# esp32-v7.net
KiCad netlist of a schematic drawn in EasyEDA Pro
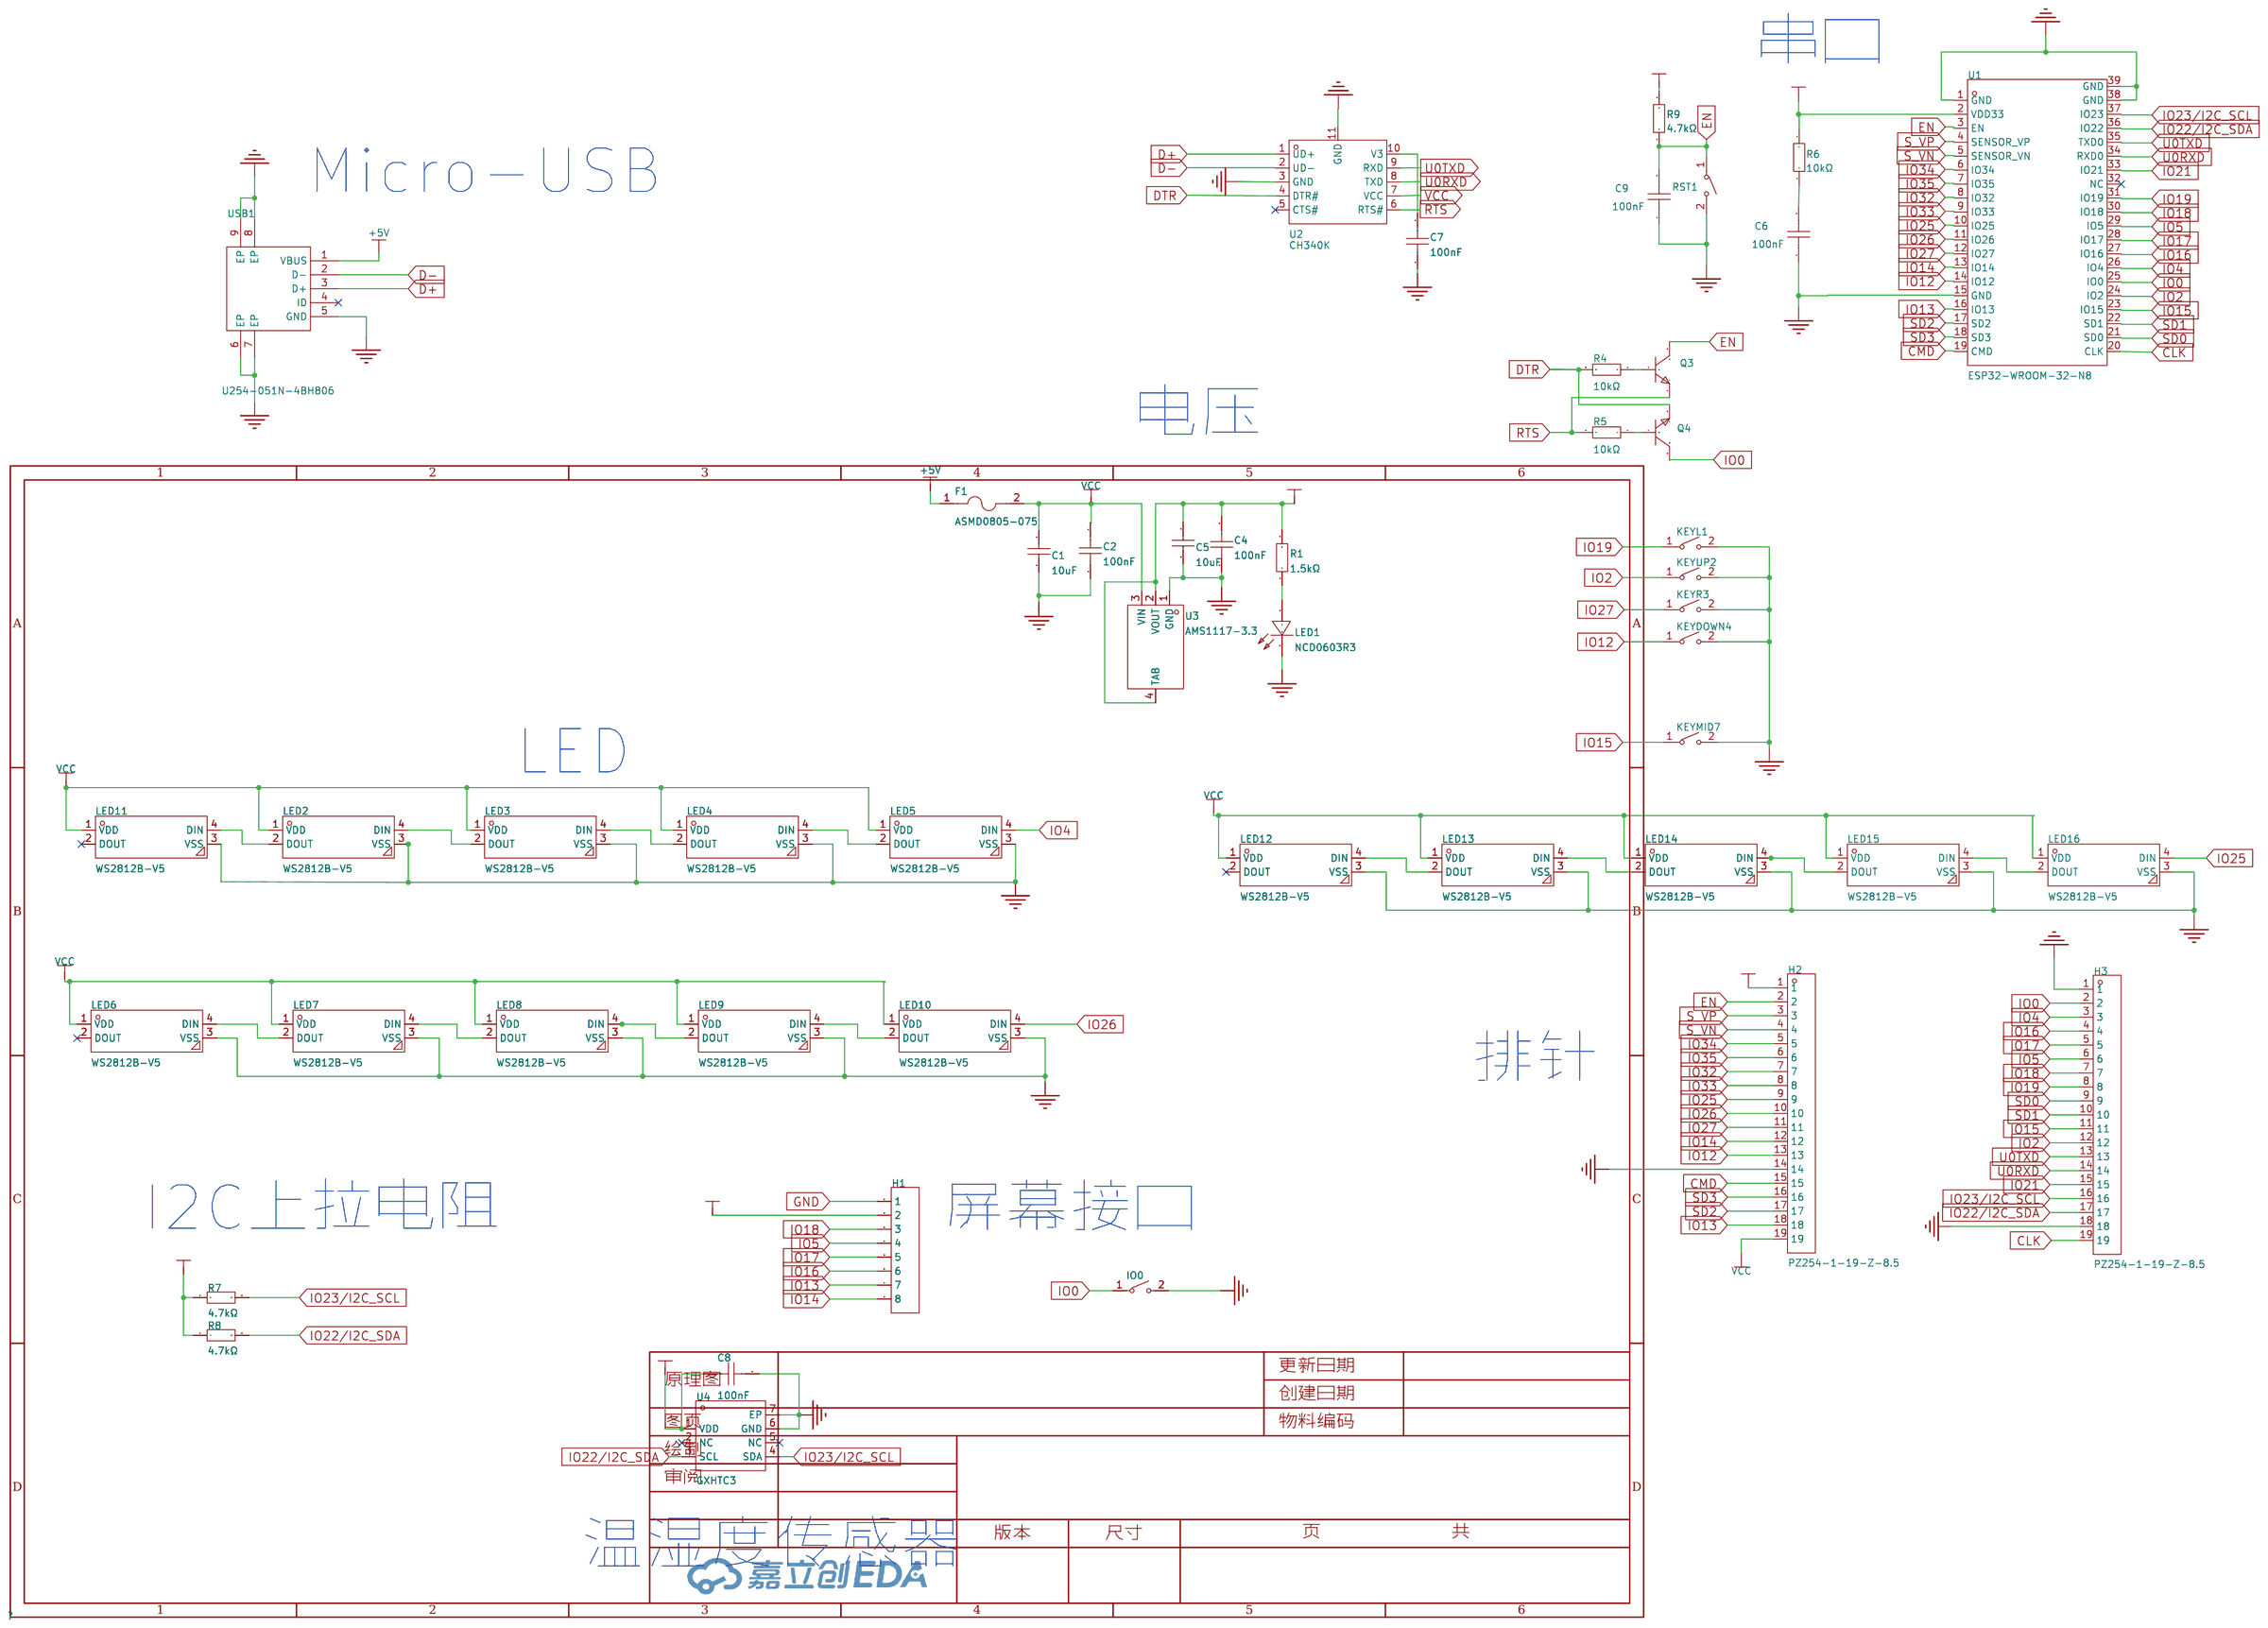
[diagram p0: schematic sheet]

(export (version "E")
  (design (tool "Eeschema 10.0.6"))
  (components
    (comp (ref "C1")
      (value "10uF")
      (footprint "easyedapro:C0805")
      (description "容值:10uF;精度:±10%;额定电压:16V;材质(温度系数):X5R;")
      (fields
        (field (name "Manufacturer Part") "CL21A106KOQNNNE")
        (field (name "Manufacturer") "SAMSUNG(三星)")
      )
      (libsource (lib "easyedapro") (part "CL21A106KOQNNNE"))
    )
    (comp (ref "C2")
      (value "100nF")
      (footprint "easyedapro:C0603")
      (description "容值:100nF;精度:±10%;额定电压:50V;材质(温度系数):X7R;")
      (fields
        (field (name "Manufacturer Part") "CC0603KRX7R9BB104")
        (field (name "Manufacturer") "YAGEO(国巨)")
      )
      (libsource (lib "easyedapro") (part "CC0603KRX7R9BB104"))
    )
    (comp (ref "C4")
      (value "100nF")
      (footprint "easyedapro:C0603")
      (description "容值:100nF;精度:±10%;额定电压:50V;材质(温度系数):X7R;")
      (fields
        (field (name "Manufacturer Part") "CC0603KRX7R9BB104")
        (field (name "Manufacturer") "YAGEO(国巨)")
      )
      (libsource (lib "easyedapro") (part "CC0603KRX7R9BB104"))
    )
    (comp (ref "C5")
      (value "10uF")
      (footprint "easyedapro:C0805")
      (description "容值:10uF;精度:±10%;额定电压:16V;材质(温度系数):X5R;")
      (fields
        (field (name "Manufacturer Part") "CL21A106KOQNNNE")
        (field (name "Manufacturer") "SAMSUNG(三星)")
      )
      (libsource (lib "easyedapro") (part "CL21A106KOQNNNE"))
    )
    (comp (ref "C6")
      (value "100nF")
      (footprint "easyedapro:C0603")
      (description "容值:100nF;精度:±10%;额定电压:50V;材质(温度系数):X7R;")
      (fields
        (field (name "Manufacturer Part") "CC0603KRX7R9BB104")
        (field (name "Manufacturer") "YAGEO(国巨)")
      )
      (libsource (lib "easyedapro") (part "CC0603KRX7R9BB104"))
    )
    (comp (ref "C7")
      (value "100nF")
      (footprint "easyedapro:C0603")
      (description "容值:100nF;精度:±10%;额定电压:50V;材质(温度系数):X7R;")
      (fields
        (field (name "Manufacturer Part") "CC0603KRX7R9BB104")
        (field (name "Manufacturer") "YAGEO(国巨)")
      )
      (libsource (lib "easyedapro") (part "CC0603KRX7R9BB104"))
    )
    (comp (ref "C8")
      (value "100nF")
      (footprint "easyedapro:C0603")
      (description "容值:100nF;精度:±10%;额定电压:50V;材质(温度系数):X7R;")
      (fields
        (field (name "Manufacturer Part") "CC0603KRX7R9BB104")
        (field (name "Manufacturer") "YAGEO(国巨)")
      )
      (libsource (lib "easyedapro") (part "CC0603KRX7R9BB104"))
    )
    (comp (ref "C9")
      (value "100nF")
      (footprint "easyedapro:C0603")
      (description "容值:100nF;精度:±10%;额定电压:50V;材质(温度系数):X7R;")
      (fields
        (field (name "Manufacturer Part") "CC0603KRX7R9BB104")
        (field (name "Manufacturer") "YAGEO(国巨)")
      )
      (libsource (lib "easyedapro") (part "CC0603KRX7R9BB104"))
    )
    (comp (ref "F1")
      (value "ASMD0805-075")
      (footprint "easyedapro:F0805")
      (description "最大电压:6V;最大电流:40A;保持电流:750mA;跳闸电流:1.5A;")
      (fields (field (name "Manufacturer") "JDTfuse(集电通)"))
      (libsource (lib "easyedapro") (part "ASMD0805-075"))
    )
    (comp (ref "H1")
      (value "~")
      (footprint "easyedapro:HDR-TH_8P-P2.54-V-F-1")
      (libsource (lib "easyedapro") (part "Header-Female-2.54_1x8"))
    )
    (comp (ref "H2")
      (value "PZ254-1-19-Z-8.5")
      (footprint "easyedapro:HDR-TH_19P-P2.54-V-M")
      (fields (field (name "Manufacturer") "HCTL(华灿天禄)"))
      (libsource (lib "easyedapro") (part "PZ254-1-19-Z-8.5"))
    )
    (comp (ref "H3")
      (value "PZ254-1-19-Z-8.5")
      (footprint "easyedapro:HDR-TH_19P-P2.54-V-M")
      (fields (field (name "Manufacturer") "HCTL(华灿天禄)"))
      (libsource (lib "easyedapro") (part "PZ254-1-19-Z-8.5"))
    )
    (comp (ref "IO0")
      (value "TS-1088R-02526")
      (footprint "easyedapro:SW-SMD_L3.9-W3.0-P4.45")
      (description "电路结构:单刀单掷;按钮形状:圆形按钮;安装方式:立贴;开关长度:3.9mm;开关宽度:2.93mm;开关高度:2.5mm;触点电流:50mA;额定电压(DC):12V;带灯:-;机械寿命:-;")
      (fields (field (name "Manufacturer") "XUNPU(讯普)"))
      (libsource (lib "easyedapro") (part "TS-1088R-02526"))
    )
    (comp (ref "KEYDOWN4")
      (value "TS-1088R-02526")
      (footprint "easyedapro:SW-SMD_L3.9-W3.0-P4.45")
      (description "电路结构:单刀单掷;按钮形状:圆形按钮;安装方式:立贴;开关长度:3.9mm;开关宽度:2.93mm;开关高度:2.5mm;触点电流:50mA;额定电压(DC):12V;带灯:-;机械寿命:-;")
      (fields (field (name "Manufacturer") "XUNPU(讯普)"))
      (libsource (lib "easyedapro") (part "TS-1088R-02526"))
    )
    (comp (ref "KEYL1")
      (value "TS-1088R-02526")
      (footprint "easyedapro:SW-SMD_L3.9-W3.0-P4.45")
      (description "电路结构:单刀单掷;按钮形状:圆形按钮;安装方式:立贴;开关长度:3.9mm;开关宽度:2.93mm;开关高度:2.5mm;触点电流:50mA;额定电压(DC):12V;带灯:-;机械寿命:-;")
      (fields (field (name "Manufacturer") "XUNPU(讯普)"))
      (libsource (lib "easyedapro") (part "TS-1088R-02526"))
    )
    (comp (ref "KEYMID7")
      (value "TS-1088R-02526")
      (footprint "easyedapro:SW-SMD_L3.9-W3.0-P4.45")
      (description "电路结构:单刀单掷;按钮形状:圆形按钮;安装方式:立贴;开关长度:3.9mm;开关宽度:2.93mm;开关高度:2.5mm;触点电流:50mA;额定电压(DC):12V;带灯:-;机械寿命:-;")
      (fields (field (name "Manufacturer") "XUNPU(讯普)"))
      (libsource (lib "easyedapro") (part "TS-1088R-02526"))
    )
    (comp (ref "KEYR3")
      (value "TS-1088R-02526")
      (footprint "easyedapro:SW-SMD_L3.9-W3.0-P4.45")
      (description "电路结构:单刀单掷;按钮形状:圆形按钮;安装方式:立贴;开关长度:3.9mm;开关宽度:2.93mm;开关高度:2.5mm;触点电流:50mA;额定电压(DC):12V;带灯:-;机械寿命:-;")
      (fields (field (name "Manufacturer") "XUNPU(讯普)"))
      (libsource (lib "easyedapro") (part "TS-1088R-02526"))
    )
    (comp (ref "KEYUP2")
      (value "TS-1088R-02526")
      (footprint "easyedapro:SW-SMD_L3.9-W3.0-P4.45")
      (description "电路结构:单刀单掷;按钮形状:圆形按钮;安装方式:立贴;开关长度:3.9mm;开关宽度:2.93mm;开关高度:2.5mm;触点电流:50mA;额定电压(DC):12V;带灯:-;机械寿命:-;")
      (fields (field (name "Manufacturer") "XUNPU(讯普)"))
      (libsource (lib "easyedapro") (part "TS-1088R-02526"))
    )
    (comp (ref "LED1")
      (value "NCD0603R3")
      (footprint "easyedapro:LED0603-R-RD_RED")
      (fields (field (name "Manufacturer") "国星光电"))
      (libsource (lib "easyedapro") (part "NCD0603R3"))
    )
    (comp (ref "LED2")
      (value "WS2812B-V5")
      (footprint "easyedapro:LED-SMD_4P-L5.0-W5.0-LS5.4-TL-1")
      (description "（注意防潮，请查阅规格书中对应具体内容）")
      (fields (field (name "Manufacturer") "worldsemi"))
      (libsource (lib "easyedapro") (part "WS2812B-V5_C2846931"))
    )
    (comp (ref "LED3")
      (value "WS2812B-V5")
      (footprint "easyedapro:LED-SMD_4P-L5.0-W5.0-LS5.4-TL-1")
      (description "（注意防潮，请查阅规格书中对应具体内容）")
      (fields (field (name "Manufacturer") "worldsemi"))
      (libsource (lib "easyedapro") (part "WS2812B-V5_C2846931"))
    )
    (comp (ref "LED4")
      (value "WS2812B-V5")
      (footprint "easyedapro:LED-SMD_4P-L5.0-W5.0-LS5.4-TL-1")
      (description "（注意防潮，请查阅规格书中对应具体内容）")
      (fields (field (name "Manufacturer") "worldsemi"))
      (libsource (lib "easyedapro") (part "WS2812B-V5_C2846931"))
    )
    (comp (ref "LED5")
      (value "WS2812B-V5")
      (footprint "easyedapro:LED-SMD_4P-L5.0-W5.0-LS5.4-TL-1")
      (description "（注意防潮，请查阅规格书中对应具体内容）")
      (fields (field (name "Manufacturer") "worldsemi"))
      (libsource (lib "easyedapro") (part "WS2812B-V5_C2846931"))
    )
    (comp (ref "LED6")
      (value "WS2812B-V5")
      (footprint "easyedapro:LED-SMD_4P-L5.0-W5.0-LS5.4-TL-1")
      (description "（注意防潮，请查阅规格书中对应具体内容）")
      (fields (field (name "Manufacturer") "worldsemi"))
      (libsource (lib "easyedapro") (part "WS2812B-V5_C2846931"))
    )
    (comp (ref "LED7")
      (value "WS2812B-V5")
      (footprint "easyedapro:LED-SMD_4P-L5.0-W5.0-LS5.4-TL-1")
      (description "（注意防潮，请查阅规格书中对应具体内容）")
      (fields (field (name "Manufacturer") "worldsemi"))
      (libsource (lib "easyedapro") (part "WS2812B-V5_C2846931"))
    )
    (comp (ref "LED8")
      (value "WS2812B-V5")
      (footprint "easyedapro:LED-SMD_4P-L5.0-W5.0-LS5.4-TL-1")
      (description "（注意防潮，请查阅规格书中对应具体内容）")
      (fields (field (name "Manufacturer") "worldsemi"))
      (libsource (lib "easyedapro") (part "WS2812B-V5_C2846931"))
    )
    (comp (ref "LED9")
      (value "WS2812B-V5")
      (footprint "easyedapro:LED-SMD_4P-L5.0-W5.0-LS5.4-TL-1")
      (description "（注意防潮，请查阅规格书中对应具体内容）")
      (fields (field (name "Manufacturer") "worldsemi"))
      (libsource (lib "easyedapro") (part "WS2812B-V5_C2846931"))
    )
    (comp (ref "LED10")
      (value "WS2812B-V5")
      (footprint "easyedapro:LED-SMD_4P-L5.0-W5.0-LS5.4-TL-1")
      (description "（注意防潮，请查阅规格书中对应具体内容）")
      (fields (field (name "Manufacturer") "worldsemi"))
      (libsource (lib "easyedapro") (part "WS2812B-V5_C2846931"))
    )
    (comp (ref "LED11")
      (value "WS2812B-V5")
      (footprint "easyedapro:LED-SMD_4P-L5.0-W5.0-LS5.4-TL-1")
      (description "（注意防潮，请查阅规格书中对应具体内容）")
      (fields (field (name "Manufacturer") "worldsemi"))
      (libsource (lib "easyedapro") (part "WS2812B-V5_C2846931"))
    )
    (comp (ref "LED12")
      (value "WS2812B-V5")
      (footprint "easyedapro:LED-SMD_4P-L5.0-W5.0-LS5.4-TL-1")
      (description "（注意防潮，请查阅规格书中对应具体内容）")
      (fields (field (name "Manufacturer") "worldsemi"))
      (libsource (lib "easyedapro") (part "WS2812B-V5_C2846931"))
    )
    (comp (ref "LED13")
      (value "WS2812B-V5")
      (footprint "easyedapro:LED-SMD_4P-L5.0-W5.0-LS5.4-TL-1")
      (description "（注意防潮，请查阅规格书中对应具体内容）")
      (fields (field (name "Manufacturer") "worldsemi"))
      (libsource (lib "easyedapro") (part "WS2812B-V5_C2846931"))
    )
    (comp (ref "LED14")
      (value "WS2812B-V5")
      (footprint "easyedapro:LED-SMD_4P-L5.0-W5.0-LS5.4-TL-1")
      (description "（注意防潮，请查阅规格书中对应具体内容）")
      (fields (field (name "Manufacturer") "worldsemi"))
      (libsource (lib "easyedapro") (part "WS2812B-V5_C2846931"))
    )
    (comp (ref "LED15")
      (value "WS2812B-V5")
      (footprint "easyedapro:LED-SMD_4P-L5.0-W5.0-LS5.4-TL-1")
      (description "（注意防潮，请查阅规格书中对应具体内容）")
      (fields (field (name "Manufacturer") "worldsemi"))
      (libsource (lib "easyedapro") (part "WS2812B-V5_C2846931"))
    )
    (comp (ref "LED16")
      (value "WS2812B-V5")
      (footprint "easyedapro:LED-SMD_4P-L5.0-W5.0-LS5.4-TL-1")
      (description "（注意防潮，请查阅规格书中对应具体内容）")
      (fields (field (name "Manufacturer") "worldsemi"))
      (libsource (lib "easyedapro") (part "WS2812B-V5_C2846931"))
    )
    (comp (ref "Q3")
      (value "L8050QLT1G")
      (footprint "easyedapro:SOT-23-3_L2.9-W1.3-P1.90-LS2.4-BR")
      (description "晶体管类型:NPN;集电极电流(Ic):800mA;集射极击穿电压(Vceo):25V;功率(Pd):225mW;")
      (fields (field (name "Manufacturer") "LRC(乐山无线电)"))
      (libsource (lib "easyedapro") (part "L8050QLT1G"))
    )
    (comp (ref "Q4")
      (value "L8050QLT1G")
      (footprint "easyedapro:SOT-23-3_L2.9-W1.3-P1.90-LS2.4-BR")
      (description "晶体管类型:NPN;集电极电流(Ic):800mA;集射极击穿电压(Vceo):25V;功率(Pd):225mW;")
      (fields (field (name "Manufacturer") "LRC(乐山无线电)"))
      (libsource (lib "easyedapro") (part "L8050QLT1G"))
    )
    (comp (ref "R1")
      (value "1.5kΩ")
      (footprint "easyedapro:R0805")
      (description "电阻类型:厚膜电阻;阻值:1.5kΩ;精度:±1%;功率:125mW;最大工作电压:150V;温度系数:±100ppm/°C;")
      (fields
        (field (name "Manufacturer Part") "0805W8F1501T5E")
        (field (name "Manufacturer") "UNI-ROYAL(厚声)")
      )
      (libsource (lib "easyedapro") (part "0805W8F1501T5E"))
    )
    (comp (ref "R4")
      (value "10kΩ")
      (footprint "easyedapro:R0603")
      (description "电阻类型:薄膜电阻;阻值:10kΩ;精度:±0.1%;功率:100mW;温度系数:±25ppm/;最大工作电压:75V;工作温度范围:-55~+155;")
      (fields
        (field (name "Manufacturer Part") "TR0603B10K0P0525Z")
        (field (name "Manufacturer") "EVER OHMS(天二科技)")
      )
      (libsource (lib "easyedapro") (part "TR0603B10KP05250.1W"))
    )
    (comp (ref "R5")
      (value "10kΩ")
      (footprint "easyedapro:R0603")
      (description "电阻类型:薄膜电阻;阻值:10kΩ;精度:±0.1%;功率:100mW;温度系数:±25ppm/;最大工作电压:75V;工作温度范围:-55~+155;")
      (fields
        (field (name "Manufacturer Part") "TR0603B10K0P0525Z")
        (field (name "Manufacturer") "EVER OHMS(天二科技)")
      )
      (libsource (lib "easyedapro") (part "TR0603B10KP05250.1W"))
    )
    (comp (ref "R6")
      (value "10kΩ")
      (footprint "easyedapro:R0603")
      (description "电阻类型:薄膜电阻;阻值:10kΩ;精度:±0.1%;功率:100mW;温度系数:±25ppm/;最大工作电压:75V;工作温度范围:-55~+155;")
      (fields
        (field (name "Manufacturer Part") "TR0603B10K0P0525Z")
        (field (name "Manufacturer") "EVER OHMS(天二科技)")
      )
      (libsource (lib "easyedapro") (part "TR0603B10KP05250.1W"))
    )
    (comp (ref "R7")
      (value "4.7kΩ")
      (footprint "easyedapro:R0805")
      (description "电阻类型:厚膜电阻;阻值:4.7kΩ;精度:±1%;功率:125mW;最大工作电压:150V;温度系数:±100ppm/°C;")
      (fields
        (field (name "Manufacturer Part") "0805W8F4701T5E")
        (field (name "Manufacturer") "UNI-ROYAL(厚声)")
      )
      (libsource (lib "easyedapro") (part "0805W8F4701T5E"))
    )
    (comp (ref "R8")
      (value "4.7kΩ")
      (footprint "easyedapro:R0805")
      (description "电阻类型:厚膜电阻;阻值:4.7kΩ;精度:±1%;功率:125mW;最大工作电压:150V;温度系数:±100ppm/°C;")
      (fields
        (field (name "Manufacturer Part") "0805W8F4701T5E")
        (field (name "Manufacturer") "UNI-ROYAL(厚声)")
      )
      (libsource (lib "easyedapro") (part "0805W8F4701T5E"))
    )
    (comp (ref "R9")
      (value "4.7kΩ")
      (footprint "easyedapro:R0805")
      (description "电阻类型:厚膜电阻;阻值:4.7kΩ;精度:±1%;功率:125mW;最大工作电压:150V;温度系数:±100ppm/°C;")
      (fields
        (field (name "Manufacturer Part") "0805W8F4701T5E")
        (field (name "Manufacturer") "UNI-ROYAL(厚声)")
      )
      (libsource (lib "easyedapro") (part "0805W8F4701T5E"))
    )
    (comp (ref "RST1")
      (value "TS-1088R-02526")
      (footprint "easyedapro:SW-SMD_L3.9-W3.0-P4.45")
      (description "电路结构:单刀单掷;按钮形状:圆形按钮;安装方式:立贴;开关长度:3.9mm;开关宽度:2.93mm;开关高度:2.5mm;触点电流:50mA;额定电压(DC):12V;带灯:-;机械寿命:-;")
      (fields (field (name "Manufacturer") "XUNPU(讯普)"))
      (libsource (lib "easyedapro") (part "TS-1088R-02526"))
    )
    (comp (ref "U1")
      (value "ESP32-WROOM-32-N8")
      (footprint "easyedapro:WIFIM-SMD_39P-L25.5-W18.0-P1.27")
      (fields (field (name "Manufacturer") "ESPRESSIF(乐鑫)"))
      (libsource (lib "easyedapro") (part "ESP32-WROOM-32(8MB)"))
    )
    (comp (ref "U2")
      (value "CH340K")
      (footprint "easyedapro:ESOP-10_L4.9-W3.9-P1.00-LS6.0-BL-EP")
      (fields (field (name "Manufacturer") "WCH(南京沁恒)"))
      (libsource (lib "easyedapro") (part "CH340K_C18208922"))
    )
    (comp (ref "U3")
      (value "AMS1117-3.3")
      (footprint "easyedapro:SOT-223-3_L6.5-W3.4-P2.30-LS7.0-BR")
      (description "输出类型:固定;最大输入电压:18V;输出电压:3.3V;最大输出电流:800mA;电源纹波抑制比(PSRR):-;输出极性:正极;")
      (fields (field (name "Manufacturer") "PUOLOP(迪浦)"))
      (libsource (lib "easyedapro") (part "AMS1117-3.3_C351784"))
    )
    (comp (ref "U4")
      (value "GXHTC3")
      (footprint "easyedapro:DFN-6_L2.0-W2.0-P0.50-BL-EP")
      (fields (field (name "Manufacturer") "GXCAS(中科银河芯)"))
      (libsource (lib "easyedapro") (part "GXHTC3"))
    )
    (comp (ref "USB1")
      (value "U254-051N-4BH806")
      (footprint "easyedapro:MICRO-USB-SMD_U254-051N-4BH806")
      (fields (field (name "Manufacturer") "XKB Connectivity(中国星坤)"))
      (libsource (lib "easyedapro") (part "U254-051N-4BH806"))
    )
  )
  (nets
    (net (code "1") (name "+5V") (class "Default")
      (node (ref "F1") (pin "1") (pinfunction "1_1") (pintype "unspecified"))
      (node (ref "USB1") (pin "1") (pinfunction "VBUS_1") (pintype "unspecified"))
    )
    (net (code "2") (name "3V3") (class "Default")
      (node (ref "C4") (pin "2") (pinfunction "2_2") (pintype "unspecified"))
      (node (ref "C5") (pin "2") (pinfunction "2_2") (pintype "input"))
      (node (ref "C8") (pin "2") (pinfunction "2_2") (pintype "unspecified"))
      (node (ref "H1") (pin "2") (pinfunction "2_2") (pintype "input"))
      (node (ref "H2") (pin "1") (pinfunction "1_1") (pintype "unspecified"))
      (node (ref "R1") (pin "2") (pinfunction "2_2") (pintype "input"))
      (node (ref "R6") (pin "1") (pinfunction "1_1") (pintype "input"))
      (node (ref "R7") (pin "1") (pinfunction "1_1") (pintype "input"))
      (node (ref "R8") (pin "1") (pinfunction "1_1") (pintype "input"))
      (node (ref "R9") (pin "2") (pinfunction "2_2") (pintype "input"))
      (node (ref "U1") (pin "2") (pinfunction "VDD33_2") (pintype "unspecified"))
      (node (ref "U3") (pin "2") (pinfunction "VOUT_2") (pintype "unspecified"))
      (node (ref "U3") (pin "4") (pinfunction "TAB_4") (pintype "unspecified"))
      (node (ref "U4") (pin "1") (pinfunction "VDD_1") (pintype "unspecified"))
    )
    (net (code "3") (name "CLK") (class "Default")
      (node (ref "H3") (pin "19") (pinfunction "19_19") (pintype "unspecified"))
      (node (ref "U1") (pin "20") (pinfunction "CLK_20") (pintype "unspecified"))
    )
    (net (code "4") (name "CMD") (class "Default")
      (node (ref "H2") (pin "15") (pinfunction "15_15") (pintype "unspecified"))
      (node (ref "U1") (pin "19") (pinfunction "CMD_19") (pintype "unspecified"))
    )
    (net (code "5") (name "D+") (class "Default")
      (node (ref "U2") (pin "1") (pinfunction "UD+_1") (pintype "unspecified"))
      (node (ref "USB1") (pin "3") (pinfunction "D+_3") (pintype "unspecified"))
    )
    (net (code "6") (name "D-") (class "Default")
      (node (ref "USB1") (pin "2") (pinfunction "D-_2") (pintype "unspecified"))
    )
    (net (code "7") (name "DTR") (class "Default")
      (node (ref "Q4") (pin "2") (pinfunction "E_2") (pintype "unspecified"))
      (node (ref "R4") (pin "2") (pinfunction "2_2") (pintype "input"))
      (node (ref "U2") (pin "4") (pinfunction "DTR#_4") (pintype "unspecified"))
    )
    (net (code "8") (name "EN") (class "Default")
      (node (ref "C9") (pin "2") (pinfunction "2_2") (pintype "unspecified"))
      (node (ref "H2") (pin "2") (pinfunction "2_2") (pintype "unspecified"))
      (node (ref "Q3") (pin "3") (pinfunction "C_3") (pintype "unspecified"))
      (node (ref "R9") (pin "1") (pinfunction "1_1") (pintype "input"))
      (node (ref "RST1") (pin "1") (pinfunction "1_1") (pintype "unspecified"))
      (node (ref "U1") (pin "3") (pinfunction "EN_3") (pintype "unspecified"))
    )
    (net (code "9") (name "GND") (class "Default")
      (node (ref "C1") (pin "1") (pinfunction "1_1") (pintype "input"))
      (node (ref "C2") (pin "1") (pinfunction "1_1") (pintype "unspecified"))
      (node (ref "C4") (pin "1") (pinfunction "1_1") (pintype "unspecified"))
      (node (ref "C5") (pin "1") (pinfunction "1_1") (pintype "input"))
      (node (ref "C6") (pin "1") (pinfunction "1_1") (pintype "unspecified"))
      (node (ref "C7") (pin "1") (pinfunction "1_1") (pintype "unspecified"))
      (node (ref "C8") (pin "1") (pinfunction "1_1") (pintype "unspecified"))
      (node (ref "C9") (pin "1") (pinfunction "1_1") (pintype "unspecified"))
      (node (ref "H1") (pin "1") (pinfunction "1_1") (pintype "input"))
      (node (ref "H2") (pin "14") (pinfunction "14_14") (pintype "unspecified"))
      (node (ref "H3") (pin "1") (pinfunction "1_1") (pintype "unspecified"))
      (node (ref "H3") (pin "18") (pinfunction "18_18") (pintype "unspecified"))
      (node (ref "IO0") (pin "2") (pinfunction "2_2") (pintype "unspecified"))
      (node (ref "KEYDOWN4") (pin "2") (pinfunction "2_2") (pintype "unspecified"))
      (node (ref "KEYL1") (pin "2") (pinfunction "2_2") (pintype "unspecified"))
      (node (ref "KEYMID7") (pin "2") (pinfunction "2_2") (pintype "unspecified"))
      (node (ref "KEYR3") (pin "2") (pinfunction "2_2") (pintype "unspecified"))
      (node (ref "KEYUP2") (pin "2") (pinfunction "2_2") (pintype "unspecified"))
      (node (ref "LED1") (pin "2") (pinfunction "K_2") (pintype "unspecified"))
      (node (ref "LED10") (pin "3") (pinfunction "VSS_3") (pintype "unspecified"))
      (node (ref "LED11") (pin "3") (pinfunction "VSS_3") (pintype "unspecified"))
      (node (ref "LED12") (pin "3") (pinfunction "VSS_3") (pintype "unspecified"))
      (node (ref "LED13") (pin "3") (pinfunction "VSS_3") (pintype "unspecified"))
      (node (ref "LED14") (pin "3") (pinfunction "VSS_3") (pintype "unspecified"))
      (node (ref "LED15") (pin "3") (pinfunction "VSS_3") (pintype "unspecified"))
      (node (ref "LED16") (pin "3") (pinfunction "VSS_3") (pintype "unspecified"))
      (node (ref "LED2") (pin "3") (pinfunction "VSS_3") (pintype "unspecified"))
      (node (ref "LED3") (pin "3") (pinfunction "VSS_3") (pintype "unspecified"))
      (node (ref "LED4") (pin "3") (pinfunction "VSS_3") (pintype "unspecified"))
      (node (ref "LED5") (pin "3") (pinfunction "VSS_3") (pintype "unspecified"))
      (node (ref "LED6") (pin "3") (pinfunction "VSS_3") (pintype "unspecified"))
      (node (ref "LED7") (pin "3") (pinfunction "VSS_3") (pintype "unspecified"))
      (node (ref "LED8") (pin "3") (pinfunction "VSS_3") (pintype "unspecified"))
      (node (ref "LED9") (pin "3") (pinfunction "VSS_3") (pintype "unspecified"))
      (node (ref "RST1") (pin "2") (pinfunction "2_2") (pintype "unspecified"))
      (node (ref "U1") (pin "15") (pinfunction "GND_15") (pintype "unspecified"))
      (node (ref "U1") (pin "39") (pinfunction "GND_39") (pintype "unspecified"))
      (node (ref "U2") (pin "11") (pinfunction "GND_11") (pintype "unspecified"))
      (node (ref "U2") (pin "3") (pinfunction "GND_3") (pintype "unspecified"))
      (node (ref "U3") (pin "1") (pinfunction "GND_1") (pintype "unspecified"))
      (node (ref "U4") (pin "6") (pinfunction "GND_6") (pintype "unspecified"))
      (node (ref "U4") (pin "7") (pinfunction "EP_7") (pintype "unspecified"))
      (node (ref "USB1") (pin "5") (pinfunction "GND_5") (pintype "unspecified"))
      (node (ref "USB1") (pin "6") (pinfunction "EP_6") (pintype "unspecified"))
      (node (ref "USB1") (pin "7") (pinfunction "EP_7") (pintype "unspecified"))
      (node (ref "USB1") (pin "8") (pinfunction "EP_8") (pintype "unspecified"))
      (node (ref "USB1") (pin "9") (pinfunction "EP_9") (pintype "unspecified"))
    )
    (net (code "10") (name "IO0") (class "Default")
      (node (ref "H3") (pin "2") (pinfunction "2_2") (pintype "unspecified"))
      (node (ref "IO0") (pin "1") (pinfunction "1_1") (pintype "unspecified"))
      (node (ref "Q4") (pin "3") (pinfunction "C_3") (pintype "unspecified"))
    )
    (net (code "11") (name "IO2") (class "Default")
      (node (ref "H3") (pin "12") (pinfunction "12_12") (pintype "unspecified"))
      (node (ref "KEYUP2") (pin "1") (pinfunction "1_1") (pintype "unspecified"))
    )
    (net (code "12") (name "IO4") (class "Default")
      (node (ref "H3") (pin "3") (pinfunction "3_3") (pintype "unspecified"))
      (node (ref "LED5") (pin "4") (pinfunction "DIN_4") (pintype "unspecified"))
    )
    (net (code "13") (name "IO5") (class "Default")
      (node (ref "H1") (pin "4") (pinfunction "4_4") (pintype "input"))
      (node (ref "H3") (pin "6") (pinfunction "6_6") (pintype "unspecified"))
    )
    (net (code "14") (name "IO12") (class "Default")
      (node (ref "H2") (pin "13") (pinfunction "13_13") (pintype "unspecified"))
      (node (ref "KEYDOWN4") (pin "1") (pinfunction "1_1") (pintype "unspecified"))
      (node (ref "U1") (pin "14") (pinfunction "IO12_14") (pintype "unspecified"))
    )
    (net (code "15") (name "IO13") (class "Default")
      (node (ref "H1") (pin "7") (pinfunction "7_7") (pintype "input"))
      (node (ref "H2") (pin "18") (pinfunction "18_18") (pintype "unspecified"))
      (node (ref "U1") (pin "16") (pinfunction "IO13_16") (pintype "unspecified"))
    )
    (net (code "16") (name "IO14") (class "Default")
      (node (ref "H1") (pin "8") (pinfunction "8_8") (pintype "input"))
      (node (ref "H2") (pin "12") (pinfunction "12_12") (pintype "unspecified"))
      (node (ref "U1") (pin "13") (pinfunction "IO14_13") (pintype "unspecified"))
    )
    (net (code "17") (name "IO15") (class "Default")
      (node (ref "H3") (pin "11") (pinfunction "11_11") (pintype "unspecified"))
      (node (ref "KEYMID7") (pin "1") (pinfunction "1_1") (pintype "unspecified"))
    )
    (net (code "18") (name "IO16") (class "Default")
      (node (ref "H1") (pin "6") (pinfunction "6_6") (pintype "input"))
      (node (ref "H3") (pin "4") (pinfunction "4_4") (pintype "unspecified"))
    )
    (net (code "19") (name "IO17") (class "Default")
      (node (ref "H1") (pin "5") (pinfunction "5_5") (pintype "input"))
      (node (ref "H3") (pin "5") (pinfunction "5_5") (pintype "unspecified"))
    )
    (net (code "20") (name "IO18") (class "Default")
      (node (ref "H1") (pin "3") (pinfunction "3_3") (pintype "input"))
      (node (ref "H3") (pin "7") (pinfunction "7_7") (pintype "unspecified"))
    )
    (net (code "21") (name "IO19") (class "Default")
      (node (ref "H3") (pin "8") (pinfunction "8_8") (pintype "unspecified"))
      (node (ref "KEYL1") (pin "1") (pinfunction "1_1") (pintype "unspecified"))
    )
    (net (code "22") (name "IO21") (class "Default")
      (node (ref "H3") (pin "15") (pinfunction "15_15") (pintype "unspecified"))
    )
    (net (code "23") (name "IO22{slash}I2C_SDA") (class "Default")
      (node (ref "H3") (pin "17") (pinfunction "17_17") (pintype "unspecified"))
      (node (ref "R8") (pin "2") (pinfunction "2_2") (pintype "input"))
      (node (ref "U4") (pin "3") (pinfunction "SCL_3") (pintype "unspecified"))
    )
    (net (code "24") (name "IO23{slash}I2C_SCL") (class "Default")
      (node (ref "H3") (pin "16") (pinfunction "16_16") (pintype "unspecified"))
      (node (ref "R7") (pin "2") (pinfunction "2_2") (pintype "input"))
      (node (ref "U4") (pin "4") (pinfunction "SDA_4") (pintype "unspecified"))
    )
    (net (code "25") (name "IO25") (class "Default")
      (node (ref "H2") (pin "9") (pinfunction "9_9") (pintype "unspecified"))
      (node (ref "LED16") (pin "4") (pinfunction "DIN_4") (pintype "unspecified"))
      (node (ref "U1") (pin "10") (pinfunction "IO25_10") (pintype "unspecified"))
    )
    (net (code "26") (name "IO26") (class "Default")
      (node (ref "H2") (pin "10") (pinfunction "10_10") (pintype "unspecified"))
      (node (ref "LED10") (pin "4") (pinfunction "DIN_4") (pintype "unspecified"))
      (node (ref "U1") (pin "11") (pinfunction "IO26_11") (pintype "unspecified"))
    )
    (net (code "27") (name "IO27") (class "Default")
      (node (ref "H2") (pin "11") (pinfunction "11_11") (pintype "unspecified"))
      (node (ref "KEYR3") (pin "1") (pinfunction "1_1") (pintype "unspecified"))
      (node (ref "U1") (pin "12") (pinfunction "IO27_12") (pintype "unspecified"))
    )
    (net (code "28") (name "IO32") (class "Default")
      (node (ref "H2") (pin "7") (pinfunction "7_7") (pintype "unspecified"))
      (node (ref "U1") (pin "8") (pinfunction "IO32_8") (pintype "unspecified"))
    )
    (net (code "29") (name "IO33") (class "Default")
      (node (ref "H2") (pin "8") (pinfunction "8_8") (pintype "unspecified"))
      (node (ref "U1") (pin "9") (pinfunction "IO33_9") (pintype "unspecified"))
    )
    (net (code "30") (name "IO34") (class "Default")
      (node (ref "H2") (pin "5") (pinfunction "5_5") (pintype "unspecified"))
      (node (ref "U1") (pin "6") (pinfunction "IO34_6") (pintype "unspecified"))
    )
    (net (code "31") (name "IO35") (class "Default")
      (node (ref "H2") (pin "6") (pinfunction "6_6") (pintype "unspecified"))
      (node (ref "U1") (pin "7") (pinfunction "IO35_7") (pintype "unspecified"))
    )
    (net (code "32") (name "Net-(C6-Pad2)") (class "Default")
      (node (ref "C6") (pin "2") (pinfunction "2_2") (pintype "unspecified"))
      (node (ref "R6") (pin "2") (pinfunction "2_2") (pintype "input"))
    )
    (net (code "33") (name "Net-(LED1-A)") (class "Default")
      (node (ref "LED1") (pin "1") (pinfunction "A_1") (pintype "unspecified"))
      (node (ref "R1") (pin "1") (pinfunction "1_1") (pintype "input"))
    )
    (net (code "34") (name "Net-(LED2-DIN)") (class "Default")
      (node (ref "LED2") (pin "4") (pinfunction "DIN_4") (pintype "unspecified"))
      (node (ref "LED3") (pin "2") (pinfunction "DOUT_2") (pintype "unspecified"))
    )
    (net (code "35") (name "Net-(LED3-DIN)") (class "Default")
      (node (ref "LED3") (pin "4") (pinfunction "DIN_4") (pintype "unspecified"))
      (node (ref "LED4") (pin "2") (pinfunction "DOUT_2") (pintype "unspecified"))
    )
    (net (code "36") (name "Net-(LED4-DIN)") (class "Default")
      (node (ref "LED4") (pin "4") (pinfunction "DIN_4") (pintype "unspecified"))
      (node (ref "LED5") (pin "2") (pinfunction "DOUT_2") (pintype "unspecified"))
    )
    (net (code "37") (name "Net-(LED6-DIN)") (class "Default")
      (node (ref "LED6") (pin "4") (pinfunction "DIN_4") (pintype "unspecified"))
      (node (ref "LED7") (pin "2") (pinfunction "DOUT_2") (pintype "unspecified"))
    )
    (net (code "38") (name "Net-(LED7-DIN)") (class "Default")
      (node (ref "LED7") (pin "4") (pinfunction "DIN_4") (pintype "unspecified"))
      (node (ref "LED8") (pin "2") (pinfunction "DOUT_2") (pintype "unspecified"))
    )
    (net (code "39") (name "Net-(LED8-DIN)") (class "Default")
      (node (ref "LED8") (pin "4") (pinfunction "DIN_4") (pintype "unspecified"))
      (node (ref "LED9") (pin "2") (pinfunction "DOUT_2") (pintype "unspecified"))
    )
    (net (code "40") (name "Net-(LED10-DOUT)") (class "Default")
      (node (ref "LED10") (pin "2") (pinfunction "DOUT_2") (pintype "unspecified"))
      (node (ref "LED9") (pin "4") (pinfunction "DIN_4") (pintype "unspecified"))
    )
    (net (code "41") (name "Net-(LED12-DIN)") (class "Default")
      (node (ref "LED12") (pin "4") (pinfunction "DIN_4") (pintype "unspecified"))
      (node (ref "LED13") (pin "2") (pinfunction "DOUT_2") (pintype "unspecified"))
    )
    (net (code "42") (name "Net-(LED13-DIN)") (class "Default")
      (node (ref "LED13") (pin "4") (pinfunction "DIN_4") (pintype "unspecified"))
      (node (ref "LED14") (pin "2") (pinfunction "DOUT_2") (pintype "unspecified"))
    )
    (net (code "43") (name "Net-(LED14-DIN)") (class "Default")
      (node (ref "LED14") (pin "4") (pinfunction "DIN_4") (pintype "unspecified"))
      (node (ref "LED15") (pin "2") (pinfunction "DOUT_2") (pintype "unspecified"))
    )
    (net (code "44") (name "Net-(LED15-DIN)") (class "Default")
      (node (ref "LED15") (pin "4") (pinfunction "DIN_4") (pintype "unspecified"))
      (node (ref "LED16") (pin "2") (pinfunction "DOUT_2") (pintype "unspecified"))
    )
    (net (code "45") (name "Net-(Q3-B)") (class "Default")
      (node (ref "Q3") (pin "1") (pinfunction "B_1") (pintype "unspecified"))
      (node (ref "R4") (pin "1") (pinfunction "1_1") (pintype "input"))
    )
    (net (code "46") (name "Net-(Q4-B)") (class "Default")
      (node (ref "Q4") (pin "1") (pinfunction "B_1") (pintype "unspecified"))
      (node (ref "R5") (pin "1") (pinfunction "1_1") (pintype "input"))
    )
    (net (code "47") (name "Net-(U2-V3)") (class "Default")
      (node (ref "C7") (pin "2") (pinfunction "2_2") (pintype "unspecified"))
      (node (ref "U2") (pin "10") (pinfunction "V3_10") (pintype "unspecified"))
    )
    (net (code "48") (name "RTS") (class "Default")
      (node (ref "Q3") (pin "2") (pinfunction "E_2") (pintype "unspecified"))
      (node (ref "R5") (pin "2") (pinfunction "2_2") (pintype "input"))
      (node (ref "U2") (pin "6") (pinfunction "RTS#_6") (pintype "unspecified"))
    )
    (net (code "49") (name "SD0") (class "Default")
      (node (ref "H3") (pin "9") (pinfunction "9_9") (pintype "unspecified"))
    )
    (net (code "50") (name "SD1") (class "Default")
      (node (ref "H3") (pin "10") (pinfunction "10_10") (pintype "unspecified"))
    )
    (net (code "51") (name "SD2") (class "Default")
      (node (ref "H2") (pin "17") (pinfunction "17_17") (pintype "unspecified"))
      (node (ref "U1") (pin "17") (pinfunction "SD2_17") (pintype "unspecified"))
    )
    (net (code "52") (name "SD3") (class "Default")
      (node (ref "H2") (pin "16") (pinfunction "16_16") (pintype "unspecified"))
      (node (ref "U1") (pin "18") (pinfunction "SD3_18") (pintype "unspecified"))
    )
    (net (code "53") (name "S_VN") (class "Default")
      (node (ref "H2") (pin "4") (pinfunction "4_4") (pintype "unspecified"))
      (node (ref "U1") (pin "5") (pinfunction "SENSOR_VN_5") (pintype "unspecified"))
    )
    (net (code "54") (name "S_VP") (class "Default")
      (node (ref "H2") (pin "3") (pinfunction "3_3") (pintype "unspecified"))
      (node (ref "U1") (pin "4") (pinfunction "SENSOR_VP_4") (pintype "unspecified"))
    )
    (net (code "55") (name "U0RXD") (class "Default")
      (node (ref "H3") (pin "14") (pinfunction "14_14") (pintype "unspecified"))
      (node (ref "U2") (pin "8") (pinfunction "TXD_8") (pintype "unspecified"))
    )
    (net (code "56") (name "U0TXD") (class "Default")
      (node (ref "H3") (pin "13") (pinfunction "13_13") (pintype "unspecified"))
      (node (ref "U2") (pin "9") (pinfunction "RXD_9") (pintype "unspecified"))
    )
    (net (code "57") (name "VCC") (class "Default")
      (node (ref "C1") (pin "2") (pinfunction "2_2") (pintype "input"))
      (node (ref "C2") (pin "2") (pinfunction "2_2") (pintype "unspecified"))
      (node (ref "F1") (pin "2") (pinfunction "2_2") (pintype "unspecified"))
      (node (ref "H2") (pin "19") (pinfunction "19_19") (pintype "unspecified"))
      (node (ref "LED10") (pin "1") (pinfunction "VDD_1") (pintype "unspecified"))
      (node (ref "LED11") (pin "1") (pinfunction "VDD_1") (pintype "unspecified"))
      (node (ref "LED12") (pin "1") (pinfunction "VDD_1") (pintype "unspecified"))
      (node (ref "LED13") (pin "1") (pinfunction "VDD_1") (pintype "unspecified"))
      (node (ref "LED14") (pin "1") (pinfunction "VDD_1") (pintype "unspecified"))
      (node (ref "LED15") (pin "1") (pinfunction "VDD_1") (pintype "unspecified"))
      (node (ref "LED16") (pin "1") (pinfunction "VDD_1") (pintype "unspecified"))
      (node (ref "LED2") (pin "1") (pinfunction "VDD_1") (pintype "unspecified"))
      (node (ref "LED3") (pin "1") (pinfunction "VDD_1") (pintype "unspecified"))
      (node (ref "LED4") (pin "1") (pinfunction "VDD_1") (pintype "unspecified"))
      (node (ref "LED5") (pin "1") (pinfunction "VDD_1") (pintype "unspecified"))
      (node (ref "LED6") (pin "1") (pinfunction "VDD_1") (pintype "unspecified"))
      (node (ref "LED7") (pin "1") (pinfunction "VDD_1") (pintype "unspecified"))
      (node (ref "LED8") (pin "1") (pinfunction "VDD_1") (pintype "unspecified"))
      (node (ref "LED9") (pin "1") (pinfunction "VDD_1") (pintype "unspecified"))
      (node (ref "U2") (pin "7") (pinfunction "VCC_7") (pintype "unspecified"))
      (node (ref "U3") (pin "3") (pinfunction "VIN_3") (pintype "unspecified"))
    )
    (net (code "58") (name "unconnected-(LED2-DOUT-Pad2)") (class "Default")
      (node (ref "LED2") (pin "2") (pinfunction "DOUT_2") (pintype "unspecified"))
    )
    (net (code "59") (name "unconnected-(LED6-DOUT-Pad2)") (class "Default")
      (node (ref "LED6") (pin "2") (pinfunction "DOUT_2") (pintype "unspecified+no_connect"))
    )
    (net (code "60") (name "unconnected-(LED11-DIN-Pad4)") (class "Default")
      (node (ref "LED11") (pin "4") (pinfunction "DIN_4") (pintype "unspecified"))
    )
    (net (code "61") (name "unconnected-(LED11-DOUT-Pad2)") (class "Default")
      (node (ref "LED11") (pin "2") (pinfunction "DOUT_2") (pintype "unspecified+no_connect"))
    )
    (net (code "62") (name "unconnected-(LED12-DOUT-Pad2)") (class "Default")
      (node (ref "LED12") (pin "2") (pinfunction "DOUT_2") (pintype "unspecified+no_connect"))
    )
    (net (code "63") (name "unconnected-(U1-GND-Pad1)") (class "Default")
      (node (ref "U1") (pin "1") (pinfunction "GND_1") (pintype "unspecified"))
    )
    (net (code "64") (name "unconnected-(U1-GND-Pad38)") (class "Default")
      (node (ref "U1") (pin "38") (pinfunction "GND_38") (pintype "unspecified"))
    )
    (net (code "65") (name "unconnected-(U1-IO0-Pad25)") (class "Default")
      (node (ref "U1") (pin "25") (pinfunction "IO0_25") (pintype "unspecified"))
    )
    (net (code "66") (name "unconnected-(U1-IO2-Pad24)") (class "Default")
      (node (ref "U1") (pin "24") (pinfunction "IO2_24") (pintype "unspecified"))
    )
    (net (code "67") (name "unconnected-(U1-IO4-Pad26)") (class "Default")
      (node (ref "U1") (pin "26") (pinfunction "IO4_26") (pintype "unspecified"))
    )
    (net (code "68") (name "unconnected-(U1-IO5-Pad29)") (class "Default")
      (node (ref "U1") (pin "29") (pinfunction "IO5_29") (pintype "unspecified"))
    )
    (net (code "69") (name "unconnected-(U1-IO15-Pad23)") (class "Default")
      (node (ref "U1") (pin "23") (pinfunction "IO15_23") (pintype "unspecified"))
    )
    (net (code "70") (name "unconnected-(U1-IO16-Pad27)") (class "Default")
      (node (ref "U1") (pin "27") (pinfunction "IO16_27") (pintype "unspecified"))
    )
    (net (code "71") (name "unconnected-(U1-IO17-Pad28)") (class "Default")
      (node (ref "U1") (pin "28") (pinfunction "IO17_28") (pintype "unspecified"))
    )
    (net (code "72") (name "unconnected-(U1-IO18-Pad30)") (class "Default")
      (node (ref "U1") (pin "30") (pinfunction "IO18_30") (pintype "unspecified"))
    )
    (net (code "73") (name "unconnected-(U1-IO19-Pad31)") (class "Default")
      (node (ref "U1") (pin "31") (pinfunction "IO19_31") (pintype "unspecified"))
    )
    (net (code "74") (name "unconnected-(U1-IO21-Pad33)") (class "Default")
      (node (ref "U1") (pin "33") (pinfunction "IO21_33") (pintype "unspecified"))
    )
    (net (code "75") (name "unconnected-(U1-IO22-Pad36)") (class "Default")
      (node (ref "U1") (pin "36") (pinfunction "IO22_36") (pintype "unspecified"))
    )
    (net (code "76") (name "unconnected-(U1-IO23-Pad37)") (class "Default")
      (node (ref "U1") (pin "37") (pinfunction "IO23_37") (pintype "unspecified"))
    )
    (net (code "77") (name "unconnected-(U1-NC-Pad32)") (class "Default")
      (node (ref "U1") (pin "32") (pinfunction "NC_32") (pintype "unspecified+no_connect"))
    )
    (net (code "78") (name "unconnected-(U1-RXD0-Pad34)") (class "Default")
      (node (ref "U1") (pin "34") (pinfunction "RXD0_34") (pintype "unspecified"))
    )
    (net (code "79") (name "unconnected-(U1-SD0-Pad21)") (class "Default")
      (node (ref "U1") (pin "21") (pinfunction "SD0_21") (pintype "unspecified"))
    )
    (net (code "80") (name "unconnected-(U1-SD1-Pad22)") (class "Default")
      (node (ref "U1") (pin "22") (pinfunction "SD1_22") (pintype "unspecified"))
    )
    (net (code "81") (name "unconnected-(U1-TXD0-Pad35)") (class "Default")
      (node (ref "U1") (pin "35") (pinfunction "TXD0_35") (pintype "unspecified"))
    )
    (net (code "82") (name "unconnected-(U2-CTS#-Pad5)") (class "Default")
      (node (ref "U2") (pin "5") (pinfunction "CTS#_5") (pintype "unspecified+no_connect"))
    )
    (net (code "83") (name "unconnected-(U2-UD--Pad2)") (class "Default")
      (node (ref "U2") (pin "2") (pinfunction "UD-_2") (pintype "unspecified"))
    )
    (net (code "84") (name "unconnected-(U4-NC-Pad2)") (class "Default")
      (node (ref "U4") (pin "2") (pinfunction "NC_2") (pintype "unspecified+no_connect"))
    )
    (net (code "85") (name "unconnected-(U4-NC-Pad5)") (class "Default")
      (node (ref "U4") (pin "5") (pinfunction "NC_5") (pintype "unspecified+no_connect"))
    )
    (net (code "86") (name "unconnected-(USB1-ID-Pad4)") (class "Default")
      (node (ref "USB1") (pin "4") (pinfunction "ID_4") (pintype "unspecified+no_connect"))
    )
  )
)
